# SRAM25616.net
KiCad netlist of a schematic drawn in Altium Designer
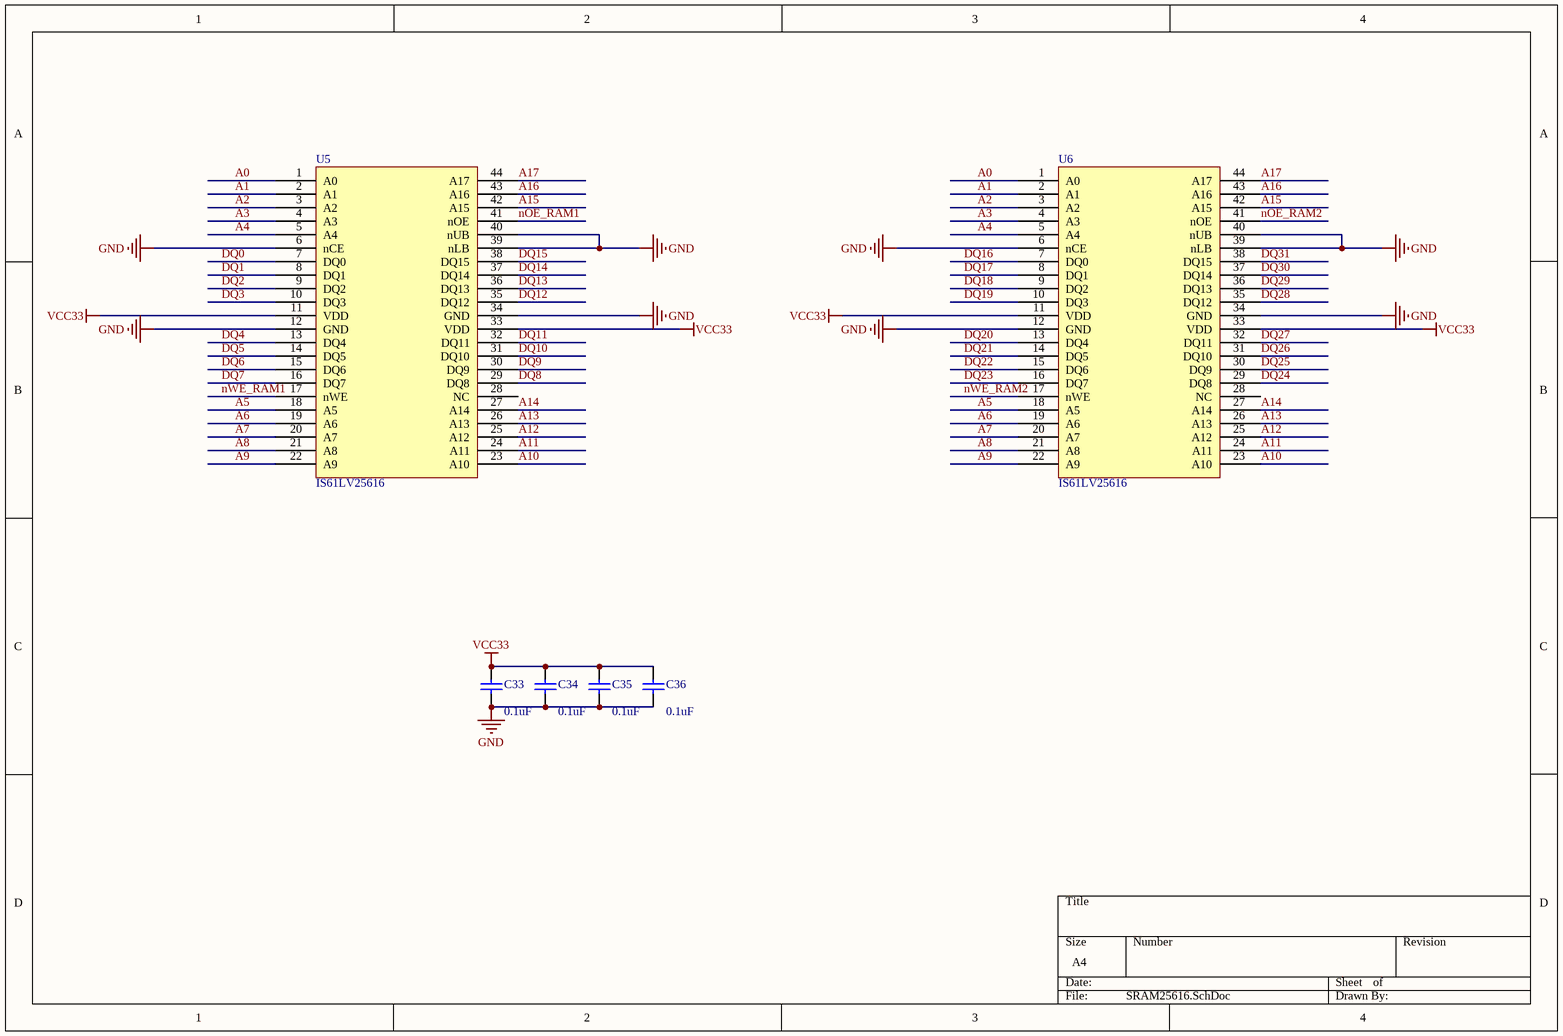
[diagram p0: SRAM25616.SchDoc]

(export (version "E")
  (design (tool "Eeschema 10.0.6"))
  (components
    (comp (ref "C33")
      (value "0.1uF")
      (footprint "cc0603")
      (description "Capacitor")
      (fields (field (name "PUBLISHER") "Altium Limited"))
      (libsource (lib "Miscellaneous Devices") (part "Cap"))
    )
    (comp (ref "C34")
      (value "0.1uF")
      (footprint "cc0603")
      (description "Capacitor")
      (fields (field (name "PUBLISHER") "Altium Limited"))
      (libsource (lib "Miscellaneous Devices") (part "Cap"))
    )
    (comp (ref "C35")
      (value "0.1uF")
      (footprint "cc0603")
      (description "Capacitor")
      (fields (field (name "PUBLISHER") "Altium Limited"))
      (libsource (lib "Miscellaneous Devices") (part "Cap"))
    )
    (comp (ref "C36")
      (value "0.1uF")
      (footprint "cc0603")
      (description "Capacitor")
      (fields (field (name "PUBLISHER") "Altium Limited"))
      (libsource (lib "Miscellaneous Devices") (part "Cap"))
    )
    (comp (ref "U5")
      (value "IS61LV25616")
      (footprint "IS61LV25616")
      (libsource (lib "LA schlib") (part "IS61LV25616"))
    )
    (comp (ref "U6")
      (value "IS61LV25616")
      (footprint "IS61LV25616")
      (libsource (lib "LA schlib") (part "IS61LV25616"))
    )
  )
  (nets
    (net (code "1") (name "/A0") (class "Default")
      (node (ref "U5") (pin "1") (pinfunction "A0_1") (pintype "passive"))
      (node (ref "U6") (pin "1") (pinfunction "A0_1") (pintype "passive"))
    )
    (net (code "2") (name "/A1") (class "Default")
      (node (ref "U5") (pin "2") (pinfunction "A1_2") (pintype "passive"))
      (node (ref "U6") (pin "2") (pinfunction "A1_2") (pintype "passive"))
    )
    (net (code "3") (name "/A2") (class "Default")
      (node (ref "U5") (pin "3") (pinfunction "A2_3") (pintype "passive"))
      (node (ref "U6") (pin "3") (pinfunction "A2_3") (pintype "passive"))
    )
    (net (code "4") (name "/A3") (class "Default")
      (node (ref "U5") (pin "4") (pinfunction "A3_4") (pintype "passive"))
      (node (ref "U6") (pin "4") (pinfunction "A3_4") (pintype "passive"))
    )
    (net (code "5") (name "/A4") (class "Default")
      (node (ref "U5") (pin "5") (pinfunction "A4_5") (pintype "passive"))
      (node (ref "U6") (pin "5") (pinfunction "A4_5") (pintype "passive"))
    )
    (net (code "6") (name "/A5") (class "Default")
      (node (ref "U5") (pin "18") (pinfunction "A5_18") (pintype "passive"))
      (node (ref "U6") (pin "18") (pinfunction "A5_18") (pintype "passive"))
    )
    (net (code "7") (name "/A6") (class "Default")
      (node (ref "U5") (pin "19") (pinfunction "A6_19") (pintype "passive"))
      (node (ref "U6") (pin "19") (pinfunction "A6_19") (pintype "passive"))
    )
    (net (code "8") (name "/A7") (class "Default")
      (node (ref "U5") (pin "20") (pinfunction "A7_20") (pintype "passive"))
      (node (ref "U6") (pin "20") (pinfunction "A7_20") (pintype "passive"))
    )
    (net (code "9") (name "/A8") (class "Default")
      (node (ref "U5") (pin "21") (pinfunction "A8_21") (pintype "passive"))
      (node (ref "U6") (pin "21") (pinfunction "A8_21") (pintype "passive"))
    )
    (net (code "10") (name "/A9") (class "Default")
      (node (ref "U5") (pin "22") (pinfunction "A9_22") (pintype "passive"))
      (node (ref "U6") (pin "22") (pinfunction "A9_22") (pintype "passive"))
    )
    (net (code "11") (name "/A10") (class "Default")
      (node (ref "U5") (pin "23") (pinfunction "A10_23") (pintype "passive"))
      (node (ref "U6") (pin "23") (pinfunction "A10_23") (pintype "passive"))
    )
    (net (code "12") (name "/A11") (class "Default")
      (node (ref "U5") (pin "24") (pinfunction "A11_24") (pintype "passive"))
      (node (ref "U6") (pin "24") (pinfunction "A11_24") (pintype "passive"))
    )
    (net (code "13") (name "/A12") (class "Default")
      (node (ref "U5") (pin "25") (pinfunction "A12_25") (pintype "passive"))
      (node (ref "U6") (pin "25") (pinfunction "A12_25") (pintype "passive"))
    )
    (net (code "14") (name "/A13") (class "Default")
      (node (ref "U5") (pin "26") (pinfunction "A13_26") (pintype "passive"))
      (node (ref "U6") (pin "26") (pinfunction "A13_26") (pintype "passive"))
    )
    (net (code "15") (name "/A14") (class "Default")
      (node (ref "U5") (pin "27") (pinfunction "A14_27") (pintype "passive"))
      (node (ref "U6") (pin "27") (pinfunction "A14_27") (pintype "passive"))
    )
    (net (code "16") (name "/A15") (class "Default")
      (node (ref "U5") (pin "42") (pinfunction "A15_42") (pintype "passive"))
      (node (ref "U6") (pin "42") (pinfunction "A15_42") (pintype "passive"))
    )
    (net (code "17") (name "/A16") (class "Default")
      (node (ref "U5") (pin "43") (pinfunction "A16_43") (pintype "passive"))
      (node (ref "U6") (pin "43") (pinfunction "A16_43") (pintype "passive"))
    )
    (net (code "18") (name "/A17") (class "Default")
      (node (ref "U5") (pin "44") (pinfunction "A17_44") (pintype "passive"))
      (node (ref "U6") (pin "44") (pinfunction "A17_44") (pintype "passive"))
    )
    (net (code "19") (name "/DQ0") (class "Default")
      (node (ref "U5") (pin "7") (pinfunction "DQ0_7") (pintype "passive"))
    )
    (net (code "20") (name "/DQ1") (class "Default")
      (node (ref "U5") (pin "8") (pinfunction "DQ1_8") (pintype "passive"))
    )
    (net (code "21") (name "/DQ2") (class "Default")
      (node (ref "U5") (pin "9") (pinfunction "DQ2_9") (pintype "passive"))
    )
    (net (code "22") (name "/DQ3") (class "Default")
      (node (ref "U5") (pin "10") (pinfunction "DQ3_10") (pintype "passive"))
    )
    (net (code "23") (name "/DQ4") (class "Default")
      (node (ref "U5") (pin "13") (pinfunction "DQ4_13") (pintype "passive"))
    )
    (net (code "24") (name "/DQ5") (class "Default")
      (node (ref "U5") (pin "14") (pinfunction "DQ5_14") (pintype "passive"))
    )
    (net (code "25") (name "/DQ6") (class "Default")
      (node (ref "U5") (pin "15") (pinfunction "DQ6_15") (pintype "passive"))
    )
    (net (code "26") (name "/DQ7") (class "Default")
      (node (ref "U5") (pin "16") (pinfunction "DQ7_16") (pintype "passive"))
    )
    (net (code "27") (name "/DQ8") (class "Default")
      (node (ref "U5") (pin "29") (pinfunction "DQ8_29") (pintype "passive"))
    )
    (net (code "28") (name "/DQ9") (class "Default")
      (node (ref "U5") (pin "30") (pinfunction "DQ9_30") (pintype "passive"))
    )
    (net (code "29") (name "/DQ10") (class "Default")
      (node (ref "U5") (pin "31") (pinfunction "DQ10_31") (pintype "passive"))
    )
    (net (code "30") (name "/DQ11") (class "Default")
      (node (ref "U5") (pin "32") (pinfunction "DQ11_32") (pintype "passive"))
    )
    (net (code "31") (name "/DQ12") (class "Default")
      (node (ref "U5") (pin "35") (pinfunction "DQ12_35") (pintype "passive"))
    )
    (net (code "32") (name "/DQ13") (class "Default")
      (node (ref "U5") (pin "36") (pinfunction "DQ13_36") (pintype "passive"))
    )
    (net (code "33") (name "/DQ14") (class "Default")
      (node (ref "U5") (pin "37") (pinfunction "DQ14_37") (pintype "passive"))
    )
    (net (code "34") (name "/DQ15") (class "Default")
      (node (ref "U5") (pin "38") (pinfunction "DQ15_38") (pintype "passive"))
    )
    (net (code "35") (name "/DQ16") (class "Default")
      (node (ref "U6") (pin "7") (pinfunction "DQ0_7") (pintype "passive"))
    )
    (net (code "36") (name "/DQ17") (class "Default")
      (node (ref "U6") (pin "8") (pinfunction "DQ1_8") (pintype "passive"))
    )
    (net (code "37") (name "/DQ18") (class "Default")
      (node (ref "U6") (pin "9") (pinfunction "DQ2_9") (pintype "passive"))
    )
    (net (code "38") (name "/DQ19") (class "Default")
      (node (ref "U6") (pin "10") (pinfunction "DQ3_10") (pintype "passive"))
    )
    (net (code "39") (name "/DQ20") (class "Default")
      (node (ref "U6") (pin "13") (pinfunction "DQ4_13") (pintype "passive"))
    )
    (net (code "40") (name "/DQ21") (class "Default")
      (node (ref "U6") (pin "14") (pinfunction "DQ5_14") (pintype "passive"))
    )
    (net (code "41") (name "/DQ22") (class "Default")
      (node (ref "U6") (pin "15") (pinfunction "DQ6_15") (pintype "passive"))
    )
    (net (code "42") (name "/DQ23") (class "Default")
      (node (ref "U6") (pin "16") (pinfunction "DQ7_16") (pintype "passive"))
    )
    (net (code "43") (name "/DQ24") (class "Default")
      (node (ref "U6") (pin "29") (pinfunction "DQ8_29") (pintype "passive"))
    )
    (net (code "44") (name "/DQ25") (class "Default")
      (node (ref "U6") (pin "30") (pinfunction "DQ9_30") (pintype "passive"))
    )
    (net (code "45") (name "/DQ26") (class "Default")
      (node (ref "U6") (pin "31") (pinfunction "DQ10_31") (pintype "passive"))
    )
    (net (code "46") (name "/DQ27") (class "Default")
      (node (ref "U6") (pin "32") (pinfunction "DQ11_32") (pintype "passive"))
    )
    (net (code "47") (name "/DQ28") (class "Default")
      (node (ref "U6") (pin "35") (pinfunction "DQ12_35") (pintype "passive"))
    )
    (net (code "48") (name "/DQ29") (class "Default")
      (node (ref "U6") (pin "36") (pinfunction "DQ13_36") (pintype "passive"))
    )
    (net (code "49") (name "/DQ30") (class "Default")
      (node (ref "U6") (pin "37") (pinfunction "DQ14_37") (pintype "passive"))
    )
    (net (code "50") (name "/DQ31") (class "Default")
      (node (ref "U6") (pin "38") (pinfunction "DQ15_38") (pintype "passive"))
    )
    (net (code "51") (name "/nOE_RAM1") (class "Default")
      (node (ref "U5") (pin "41") (pinfunction "nOE_41") (pintype "passive"))
    )
    (net (code "52") (name "/nOE_RAM2") (class "Default")
      (node (ref "U6") (pin "41") (pinfunction "nOE_41") (pintype "passive"))
    )
    (net (code "53") (name "/nWE_RAM1") (class "Default")
      (node (ref "U5") (pin "17") (pinfunction "nWE_17") (pintype "passive"))
    )
    (net (code "54") (name "/nWE_RAM2") (class "Default")
      (node (ref "U6") (pin "17") (pinfunction "nWE_17") (pintype "passive"))
    )
    (net (code "55") (name "GND") (class "Default")
      (node (ref "C33") (pin "1") (pinfunction "1_1") (pintype "passive"))
      (node (ref "C34") (pin "1") (pinfunction "1_1") (pintype "passive"))
      (node (ref "C35") (pin "1") (pinfunction "1_1") (pintype "passive"))
      (node (ref "C36") (pin "1") (pinfunction "1_1") (pintype "passive"))
      (node (ref "U5") (pin "12") (pinfunction "GND_12") (pintype "passive"))
      (node (ref "U5") (pin "34") (pinfunction "GND_34") (pintype "passive"))
      (node (ref "U5") (pin "39") (pinfunction "nLB_39") (pintype "passive"))
      (node (ref "U5") (pin "40") (pinfunction "nUB_40") (pintype "passive"))
      (node (ref "U5") (pin "6") (pinfunction "nCE_6") (pintype "passive"))
      (node (ref "U6") (pin "12") (pinfunction "GND_12") (pintype "passive"))
      (node (ref "U6") (pin "34") (pinfunction "GND_34") (pintype "passive"))
      (node (ref "U6") (pin "39") (pinfunction "nLB_39") (pintype "passive"))
      (node (ref "U6") (pin "40") (pinfunction "nUB_40") (pintype "passive"))
      (node (ref "U6") (pin "6") (pinfunction "nCE_6") (pintype "passive"))
    )
    (net (code "56") (name "VCC33") (class "Default")
      (node (ref "C33") (pin "2") (pinfunction "2_2") (pintype "passive"))
      (node (ref "C34") (pin "2") (pinfunction "2_2") (pintype "passive"))
      (node (ref "C35") (pin "2") (pinfunction "2_2") (pintype "passive"))
      (node (ref "C36") (pin "2") (pinfunction "2_2") (pintype "passive"))
      (node (ref "U5") (pin "11") (pinfunction "VDD_11") (pintype "passive"))
      (node (ref "U5") (pin "33") (pinfunction "VDD_33") (pintype "passive"))
      (node (ref "U6") (pin "11") (pinfunction "VDD_11") (pintype "passive"))
      (node (ref "U6") (pin "33") (pinfunction "VDD_33") (pintype "passive"))
    )
    (net (code "57") (name "unconnected-(U5-NC-Pad28)") (class "Default")
      (node (ref "U5") (pin "28") (pinfunction "NC_28") (pintype "passive"))
    )
    (net (code "58") (name "unconnected-(U6-NC-Pad28)") (class "Default")
      (node (ref "U6") (pin "28") (pinfunction "NC_28") (pintype "passive"))
    )
  )
)
